# H19R1_Frontend_1.net
KiCad netlist of a schematic drawn in Altium Designer
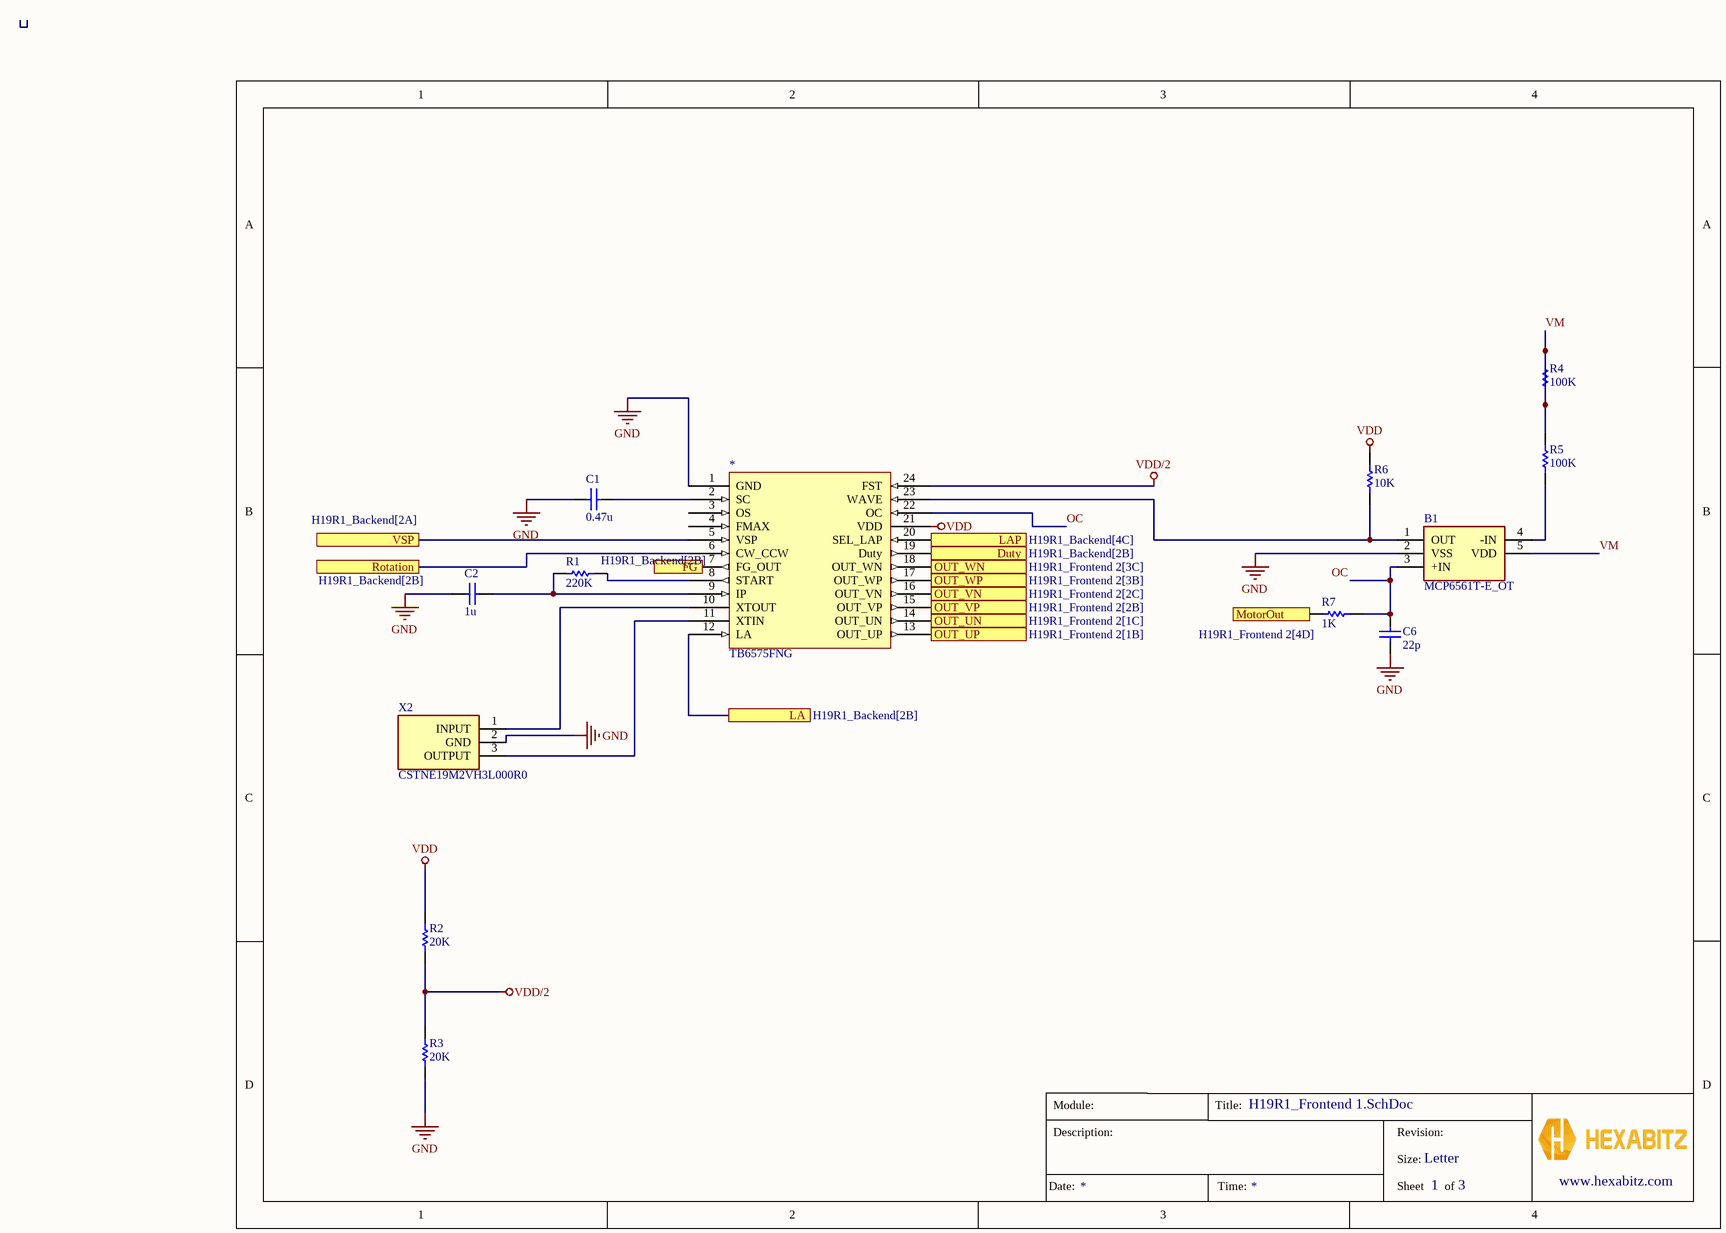
[diagram p0: H19R1_Frontend 1.SchDoc]

(export (version "E")
  (design (tool "Eeschema 10.0.6"))
  (components
    (comp (ref "*") (value "TB6575FNG") (libsource (lib "toshiba") (part "TB6575FNG")))
    (comp (ref "B1")
      (value "MCP6561T-E_OT")
      (footprint "SOT95P270X145-5N")
      (description "Single 1.8V Push/Pull Comparator, E temp")
      (fields (field (name "MANUFACTURER_PART_NUMBER") "MCP6561T-E/OT"))
      (libsource (lib "MCP6561T-E_OT") (part "MCP6561T-E_OT"))
    )
    (comp (ref "C1")
      (value "0.47u")
      (description "Capacitor")
      (libsource (lib "Simulation Generic Components") (part "Capacitor"))
    )
    (comp (ref "C2")
      (value "1u")
      (description "Capacitor")
      (libsource (lib "Simulation Generic Components") (part "Capacitor"))
    )
    (comp (ref "C6")
      (value "22p")
      (description "Capacitor")
      (libsource (lib "Simulation Generic Components") (part "Capacitor"))
    )
    (comp (ref "R1")
      (value "220K")
      (description "Resistor")
      (libsource (lib "Simulation Generic Components") (part "Resistor"))
    )
    (comp (ref "R2")
      (value "20K")
      (description "Resistor")
      (libsource (lib "Simulation Generic Components") (part "Resistor"))
    )
    (comp (ref "R3")
      (value "20K")
      (description "Resistor")
      (libsource (lib "Simulation Generic Components") (part "Resistor"))
    )
    (comp (ref "R4")
      (value "100K")
      (description "Resistor")
      (libsource (lib "Simulation Generic Components") (part "Resistor"))
    )
    (comp (ref "R5")
      (value "100K")
      (description "Resistor")
      (libsource (lib "Simulation Generic Components") (part "Resistor"))
    )
    (comp (ref "R6")
      (value "10K")
      (description "Resistor")
      (libsource (lib "Simulation Generic Components") (part "Resistor"))
    )
    (comp (ref "R7")
      (value "1K")
      (description "Resistor")
      (libsource (lib "Simulation Generic Components") (part "Resistor"))
    )
    (comp (ref "X2")
      (value "CSTNE19M2VH3L000R0")
      (footprint "CSTNE19M2VH3L000R0")
      (description "19.2 MHz Ceramic Resonator Built in Capacitor 15 pF +/-0.11% -40C ~ 85C Surface Mount")
      (fields (field (name "MOUSER PART NUMBER") "81-CSTNE19M2VH3L000R"))
      (libsource (lib "CSTNE19M2VH3L000R0") (part "CSTNE19M2VH3L000R0"))
    )
  )
  (nets
    (net (code "1") (name "/Duty") (class "Default")
      (node (ref "*") (pin "19") (pinfunction "Duty_19") (pintype "output"))
    )
    (net (code "3") (name "/LA") (class "Default")
      (node (ref "*") (pin "12") (pinfunction "LA_12") (pintype "input"))
    )
    (net (code "4") (name "/LAP") (class "Default")
      (node (ref "*") (pin "20") (pinfunction "SEL_LAP_20") (pintype "input"))
    )
    (net (code "5") (name "/MotorOut") (class "Default")
      (node (ref "R7") (pin "1") (pinfunction "1_1") (pintype "passive"))
    )
    (net (code "6") (name "/OC") (class "Default")
      (node (ref "*") (pin "22") (pinfunction "OC_22") (pintype "input"))
      (node (ref "B1") (pin "3") (pinfunction "+IN_3") (pintype "passive"))
      (node (ref "C6") (pin "2") (pinfunction "2_2") (pintype "passive"))
      (node (ref "R7") (pin "2") (pinfunction "2_2") (pintype "passive"))
    )
    (net (code "7") (name "/OUT_UN") (class "Default")
      (node (ref "*") (pin "14") (pinfunction "OUT_UN_14") (pintype "output"))
    )
    (net (code "8") (name "/OUT_UP") (class "Default")
      (node (ref "*") (pin "13") (pinfunction "OUT_UP_13") (pintype "output"))
    )
    (net (code "9") (name "/OUT_VN") (class "Default")
      (node (ref "*") (pin "16") (pinfunction "OUT_VN_16") (pintype "output"))
    )
    (net (code "10") (name "/OUT_VP") (class "Default")
      (node (ref "*") (pin "15") (pinfunction "OUT_VP_15") (pintype "output"))
    )
    (net (code "11") (name "/OUT_WN") (class "Default")
      (node (ref "*") (pin "18") (pinfunction "OUT_WN_18") (pintype "output"))
    )
    (net (code "12") (name "/OUT_WP") (class "Default")
      (node (ref "*") (pin "17") (pinfunction "OUT_WP_17") (pintype "output"))
    )
    (net (code "13") (name "/Rotation") (class "Default")
      (node (ref "*") (pin "6") (pinfunction "CW_CCW_6") (pintype "input"))
    )
    (net (code "14") (name "/VM") (class "Default")
      (node (ref "B1") (pin "5") (pinfunction "VDD_5") (pintype "passive"))
      (node (ref "R4") (pin "1") (pinfunction "1_1") (pintype "passive"))
      (node (ref "R4") (pin "2") (pinfunction "2_2") (pintype "passive"))
      (node (ref "R5") (pin "2") (pinfunction "2_2") (pintype "passive"))
    )
    (net (code "15") (name "/VSP") (class "Default")
      (node (ref "*") (pin "5") (pinfunction "VSP_5") (pintype "input"))
    )
    (net (code "16") (name "GND") (class "Default")
      (node (ref "*") (pin "1") (pinfunction "GND_1") (pintype "power_in"))
      (node (ref "B1") (pin "2") (pinfunction "VSS_2") (pintype "passive"))
      (node (ref "C1") (pin "1") (pinfunction "1_1") (pintype "passive"))
      (node (ref "C2") (pin "1") (pinfunction "1_1") (pintype "passive"))
      (node (ref "C6") (pin "1") (pinfunction "1_1") (pintype "passive"))
      (node (ref "R3") (pin "1") (pinfunction "1_1") (pintype "passive"))
      (node (ref "X2") (pin "2") (pinfunction "GND_2") (pintype "passive"))
    )
    (net (code "17") (name "Net-(*-IP)") (class "Default")
      (node (ref "*") (pin "9") (pinfunction "IP_9") (pintype "input"))
      (node (ref "C2") (pin "2") (pinfunction "2_2") (pintype "passive"))
      (node (ref "R1") (pin "1") (pinfunction "1_1") (pintype "passive"))
    )
    (net (code "18") (name "Net-(*-SC)") (class "Default")
      (node (ref "*") (pin "2") (pinfunction "SC_2") (pintype "input"))
      (node (ref "C1") (pin "2") (pinfunction "2_2") (pintype "passive"))
    )
    (net (code "19") (name "Net-(*-START)") (class "Default")
      (node (ref "*") (pin "8") (pinfunction "START_8") (pintype "output"))
      (node (ref "R1") (pin "2") (pinfunction "2_2") (pintype "passive"))
    )
    (net (code "20") (name "Net-(*-WAVE)") (class "Default")
      (node (ref "*") (pin "23") (pinfunction "WAVE_23") (pintype "input"))
      (node (ref "B1") (pin "1") (pinfunction "OUT_1") (pintype "passive"))
      (node (ref "R6") (pin "1") (pinfunction "1_1") (pintype "passive"))
    )
    (net (code "21") (name "Net-(*-XTIN)") (class "Default")
      (node (ref "*") (pin "11") (pinfunction "XTIN_11") (pintype "passive"))
      (node (ref "X2") (pin "3") (pinfunction "OUTPUT_3") (pintype "passive"))
    )
    (net (code "22") (name "Net-(*-XTOUT)") (class "Default")
      (node (ref "*") (pin "10") (pinfunction "XTOUT_10") (pintype "passive"))
      (node (ref "X2") (pin "1") (pinfunction "INPUT_1") (pintype "passive"))
    )
    (net (code "23") (name "Net-(B1--IN)") (class "Default")
      (node (ref "B1") (pin "4") (pinfunction "-IN_4") (pintype "passive"))
      (node (ref "R5") (pin "1") (pinfunction "1_1") (pintype "passive"))
    )
    (net (code "24") (name "VDD") (class "Default")
      (node (ref "*") (pin "21") (pinfunction "VDD_21") (pintype "power_in"))
      (node (ref "R2") (pin "2") (pinfunction "2_2") (pintype "passive"))
      (node (ref "R6") (pin "2") (pinfunction "2_2") (pintype "passive"))
    )
    (net (code "25") (name "VDD{slash}2") (class "Default")
      (node (ref "*") (pin "24") (pinfunction "FST_24") (pintype "input"))
      (node (ref "R2") (pin "1") (pinfunction "1_1") (pintype "passive"))
      (node (ref "R3") (pin "2") (pinfunction "2_2") (pintype "passive"))
    )
    (net (code "26") (name "unconnected-(*-FG_OUT-Pad7)") (class "Default")
      (node (ref "*") (pin "7") (pinfunction "FG_OUT_7") (pintype "output"))
    )
    (net (code "27") (name "unconnected-(*-FMAX-Pad4)") (class "Default")
      (node (ref "*") (pin "4") (pinfunction "FMAX_4") (pintype "input"))
    )
    (net (code "28") (name "unconnected-(*-OS-Pad3)") (class "Default")
      (node (ref "*") (pin "3") (pinfunction "OS_3") (pintype "input"))
    )
  )
)
